# 3_3V2_5A_Microcontroller_Power.net
KiCad netlist of a schematic drawn in Altium Designer
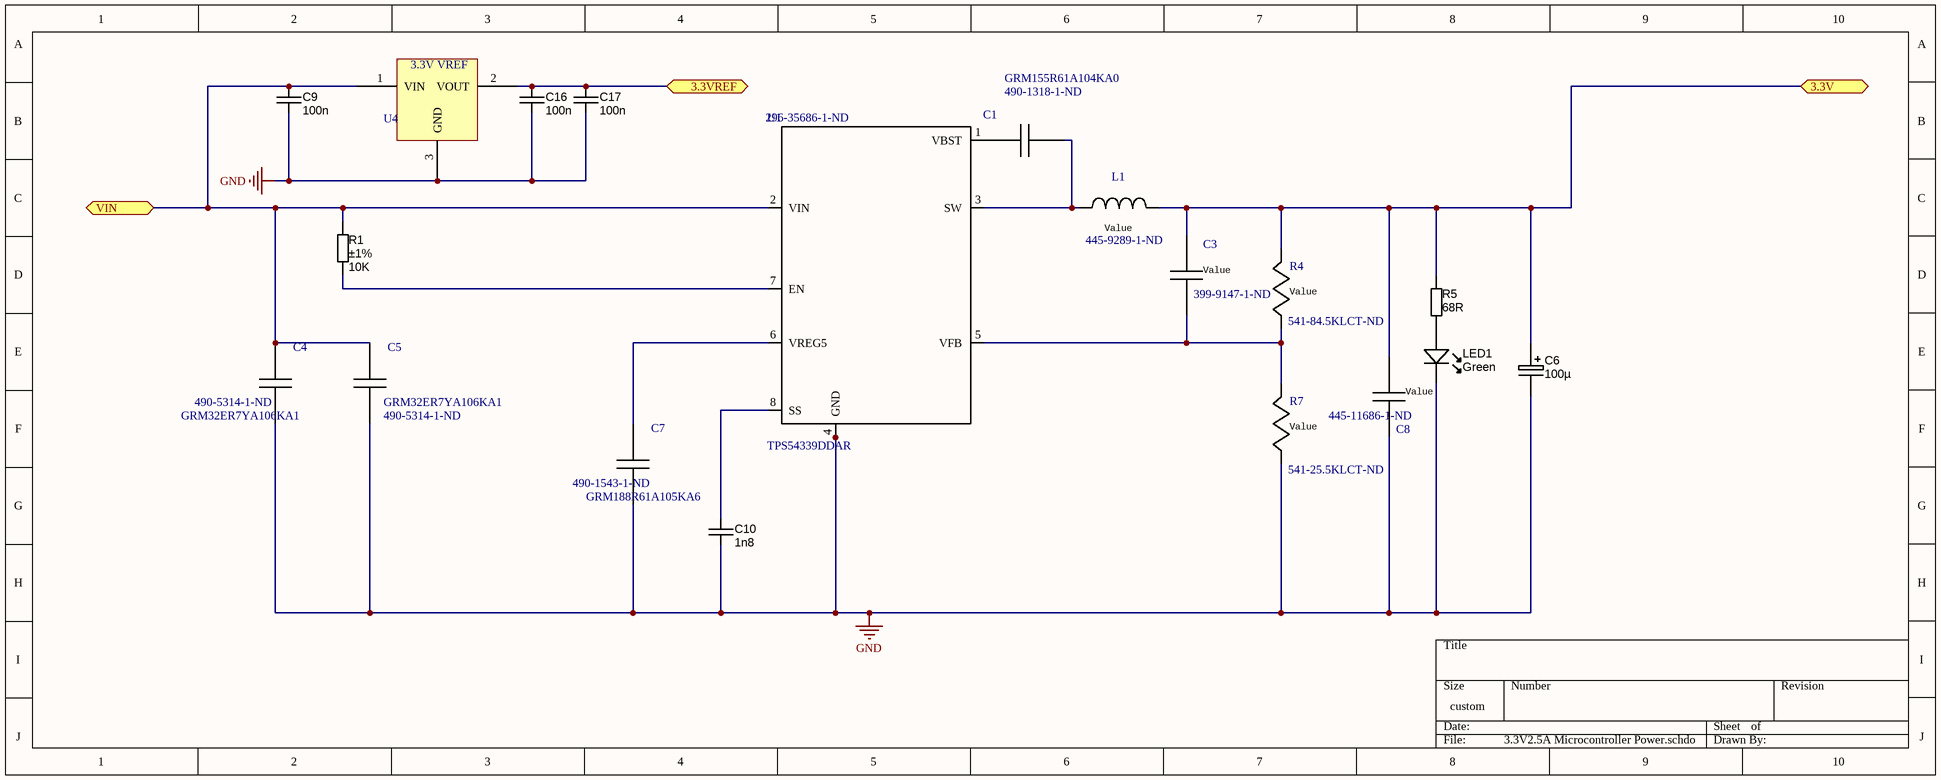
[diagram p0: 3.3V2.5A Microcontroller Power.schdoc]

(export (version "E")
  (design (tool "Eeschema 10.0.6"))
  (components
    (comp (ref "C1")
      (value "GRM155R61A104KA0")
      (footprint "0402")
      (description "Imported")
      (fields
        (field (name "MANUFACTURER_PART_NUMBER") "GRM155R61A104KA01D")
        (field (name "SUPPLIER PART NUMBER 1") "490-1318-1-ND")
      )
      (libsource (lib "LIB1") (part "GRM155R61A104KA0"))
    )
    (comp (ref "C3")
      (value "Value")
      (footprint "0805")
      (description "Imported")
      (fields
        (field (name "MANUFACTURER_PART_NUMBER") "C0805C100M4GACTU")
        (field (name "SUPPLIER PART NUMBER 1") "399-9147-1-ND")
      )
      (libsource (lib "LIB1") (part "C0805C100M4GACTU"))
    )
    (comp (ref "C4")
      (value "GRM32ER7YA106KA1")
      (footprint "1210_280")
      (description "Imported")
      (fields
        (field (name "MANUFACTURER_PART_NUMBER") "GRM32ER7YA106KA12L")
        (field (name "SUPPLIER PART NUMBER 1") "490-5314-1-ND")
      )
      (libsource (lib "LIB1") (part "GRM32ER7YA106KA1"))
    )
    (comp (ref "C5")
      (value "GRM32ER7YA106KA1")
      (footprint "1210_280")
      (description "Imported")
      (fields
        (field (name "MANUFACTURER_PART_NUMBER") "GRM32ER7YA106KA12L")
        (field (name "SUPPLIER PART NUMBER 1") "490-5314-1-ND")
      )
      (libsource (lib "LIB1") (part "GRM32ER7YA106KA1"))
    )
    (comp (ref "C6")
      (value "100µ")
      (footprint "CAPMP7343X310N")
      (description "Capacitor SMD Tantalum 100uF 20% 103V  2917")
      (fields
        (field (name "MANUFACTURER PART NUMBER") "T520D107M010ATE080")
        (field (name "TOLERANCE") "±20%")
      )
      (libsource (lib "PBL - Capacitors") (part "CAPTP_100u_2917_10V"))
    )
    (comp (ref "C7")
      (value "GRM188R61A105KA6")
      (footprint "0603")
      (description "Imported")
      (fields
        (field (name "MANUFACTURER_PART_NUMBER") "GRM188R61A105KA61D")
        (field (name "SUPPLIER PART NUMBER 1") "490-1543-1-ND")
      )
      (libsource (lib "LIB1") (part "GRM188R61A105KA6"))
    )
    (comp (ref "C8")
      (value "Value")
      (footprint "1206")
      (description "Imported")
      (fields
        (field (name "MANUFACTURER_PART_NUMBER") "C3216JB1A476M")
        (field (name "SUPPLIER PART NUMBER 1") "445-11686-1-ND")
      )
      (libsource (lib "LIB1") (part "C3216JB1A476M"))
    )
    (comp (ref "C9")
      (value "100n")
      (footprint "CAPC1608X90N")
      (description "Capacitor SMD Cer 100nF 10% 50V X7R 0603")
      (fields
        (field (name "TOLERANCE") "±10%")
        (field (name "MANUFACTURER") "Murata Electronics North America")
      )
      (libsource (lib "PBL - Capacitors") (part "CAPC_100n_0603_X7R_50V_10%"))
    )
    (comp (ref "C10")
      (value "1n8")
      (footprint "CAPC2012X135N")
      (description "Capacitor SMD Cer 1.8nF 10% 50V X7R 0805")
      (fields (field (name "TOLERANCE") "±10%") (field (name "Comment") "approved sub OK"))
      (libsource (lib "PBL - Capacitors") (part "CAPC_1n8_50V_0805"))
    )
    (comp (ref "C16")
      (value "100n")
      (footprint "CAPC1608X90N")
      (description "Capacitor SMD Cer 100nF 10% 50V X7R 0603")
      (fields
        (field (name "TOLERANCE") "±10%")
        (field (name "MANUFACTURER") "Murata Electronics North America")
      )
      (libsource (lib "PBL - Capacitors") (part "CAPC_100n_0603_X7R_50V_10%"))
    )
    (comp (ref "C17")
      (value "100n")
      (footprint "CAPC1608X90N")
      (description "Capacitor SMD Cer 100nF 10% 50V X7R 0603")
      (fields
        (field (name "TOLERANCE") "±10%")
        (field (name "MANUFACTURER") "Murata Electronics North America")
      )
      (libsource (lib "PBL - Capacitors") (part "CAPC_100n_0603_X7R_50V_10%"))
    )
    (comp (ref "L1")
      (value "Value")
      (footprint "CLF7045")
      (description "Imported")
      (fields
        (field (name "MANUFACTURER_PART_NUMBER") "CLF7045T-3R3N")
        (field (name "MANUFACTURER") "TDK")
        (field (name "SUPPLIER PART NUMBER 1") "445-9289-1-ND")
      )
      (libsource (lib "LIB1") (part "CLF7045T-3R3N"))
    )
    (comp (ref "LED1")
      (value "Green")
      (footprint "LED-0603-GREEN")
      (description "LED 0603 SMD Green 525nm 350mcd 20mA")
      (libsource (lib "PBL - Light Sources") (part "LED_SMD_Green_0603_525nm_350mcd"))
    )
    (comp (ref "R1")
      (value "10K")
      (footprint "RESC1005X40N")
      (description "Resistor SMD chip 10k Ohm 0.063W 1% 0402")
      (fields (field (name "TOLERANCE") "±1%") (field (name "Comment") "Thick Film"))
      (libsource (lib "PBL - Resistors") (part "RES_10K_0402_1%"))
    )
    (comp (ref "R4")
      (value "Value")
      (footprint "0402")
      (description "Imported")
      (fields
        (field (name "MANUFACTURER_PART_NUMBER") "CRCW040284K5FKED")
        (field (name "SUPPLIER PART NUMBER 1") "541-84.5KLCT-ND")
      )
      (libsource (lib "LIB1") (part "CRCW040284K5FKED"))
    )
    (comp (ref "R5")
      (value "68R")
      (footprint "RESC1005X40N")
      (description "Resistor SMD chip 68 Ohm 0.063W 5% 0402")
      (fields (field (name "TOLERANCE") "±5%") (field (name "Comment") "Thick Film"))
      (libsource (lib "PBL - Resistors") (part "RES_68R_0402_5%"))
    )
    (comp (ref "R7")
      (value "Value")
      (footprint "0402")
      (description "Imported")
      (fields
        (field (name "MANUFACTURER_PART_NUMBER") "CRCW040225K5FKED")
        (field (name "SUPPLIER PART NUMBER 1") "541-25.5KLCT-ND")
      )
      (libsource (lib "LIB1") (part "CRCW040225K5FKED"))
    )
    (comp (ref "U1")
      (value "TPS54339DDAR")
      (footprint "DDA0008E")
      (description "Imported")
      (fields
        (field (name "MANUFACTURER_PART_NUMBER") "TPS54229DDAR")
        (field (name "SUPPLIER PART NUMBER 1") "296-35686-1-ND")
      )
      (libsource (lib "LIB1") (part "TPS54339DDAR"))
    )
    (comp (ref "U4")
      (value "NCP51460SN33T1G")
      (footprint "SOT23-3")
      (description "Series Voltage Reference IC ±1% 20mA TO-236-3, SC-59, SOT-23-3")
      (libsource (lib "PBL - Regulators") (part "VREF_3.3_NCP51460SN33T1G"))
    )
  )
  (nets
    (net (code "1") (name "/3.3V") (class "Default")
      (node (ref "C3") (pin "1") (pinfunction "1_1") (pintype "passive"))
      (node (ref "C6") (pin "1") (pintype "passive"))
      (node (ref "C8") (pin "1") (pinfunction "1_1") (pintype "passive"))
      (node (ref "L1") (pin "1") (pinfunction "1_1") (pintype "passive"))
      (node (ref "R4") (pin "1") (pinfunction "1_1") (pintype "passive"))
      (node (ref "R5") (pin "1") (pinfunction "1_1") (pintype "passive"))
    )
    (net (code "2") (name "/3.3VREF") (class "Default")
      (node (ref "C16") (pin "1") (pintype "passive"))
      (node (ref "C17") (pin "1") (pintype "passive"))
      (node (ref "U4") (pin "2") (pinfunction "VOUT_2") (pintype "passive"))
    )
    (net (code "3") (name "/VIN") (class "Default")
      (node (ref "C4") (pin "1") (pinfunction "1_1") (pintype "passive"))
      (node (ref "C5") (pin "1") (pinfunction "1_1") (pintype "passive"))
      (node (ref "C9") (pin "1") (pintype "passive"))
      (node (ref "R1") (pin "1") (pinfunction "1_1") (pintype "passive"))
      (node (ref "U1") (pin "2") (pinfunction "VIN_2") (pintype "passive"))
      (node (ref "U4") (pin "1") (pinfunction "VIN_1") (pintype "passive"))
    )
    (net (code "4") (name "GND") (class "Default")
      (node (ref "C10") (pin "2") (pintype "passive"))
      (node (ref "C16") (pin "2") (pintype "passive"))
      (node (ref "C17") (pin "2") (pintype "passive"))
      (node (ref "C4") (pin "2") (pinfunction "2_2") (pintype "passive"))
      (node (ref "C5") (pin "2") (pinfunction "2_2") (pintype "passive"))
      (node (ref "C6") (pin "2") (pintype "passive"))
      (node (ref "C7") (pin "2") (pinfunction "2_2") (pintype "passive"))
      (node (ref "C8") (pin "2") (pinfunction "2_2") (pintype "passive"))
      (node (ref "C9") (pin "2") (pintype "passive"))
      (node (ref "LED1") (pin "K") (pinfunction "K_K") (pintype "passive"))
      (node (ref "R7") (pin "2") (pinfunction "2_2") (pintype "passive"))
      (node (ref "U1") (pin "4") (pinfunction "GND_4") (pintype "passive"))
      (node (ref "U1") (pin "9") (pinfunction "GND_9") (pintype "passive"))
      (node (ref "U4") (pin "3") (pinfunction "GND_3") (pintype "passive"))
    )
    (net (code "5") (name "Net-(LED1-PadA)") (class "Default")
      (node (ref "LED1") (pin "A") (pinfunction "A_A") (pintype "passive"))
      (node (ref "R5") (pin "2") (pinfunction "2_2") (pintype "passive"))
    )
    (net (code "6") (name "Net-(U1-EN)") (class "Default")
      (node (ref "R1") (pin "2") (pinfunction "2_2") (pintype "passive"))
      (node (ref "U1") (pin "7") (pinfunction "EN_7") (pintype "passive"))
    )
    (net (code "7") (name "Net-(U1-SS)") (class "Default")
      (node (ref "C10") (pin "1") (pintype "passive"))
      (node (ref "U1") (pin "8") (pinfunction "SS_8") (pintype "passive"))
    )
    (net (code "8") (name "Net-(U1-SW)") (class "Default")
      (node (ref "C1") (pin "2") (pinfunction "2_2") (pintype "passive"))
      (node (ref "L1") (pin "2") (pinfunction "2_2") (pintype "passive"))
      (node (ref "U1") (pin "3") (pinfunction "SW_3") (pintype "passive"))
    )
    (net (code "9") (name "Net-(U1-VBST)") (class "Default")
      (node (ref "C1") (pin "1") (pinfunction "1_1") (pintype "passive"))
      (node (ref "U1") (pin "1") (pinfunction "VBST_1") (pintype "passive"))
    )
    (net (code "10") (name "Net-(U1-VFB)") (class "Default")
      (node (ref "C3") (pin "2") (pinfunction "2_2") (pintype "passive"))
      (node (ref "R4") (pin "2") (pinfunction "2_2") (pintype "passive"))
      (node (ref "R7") (pin "1") (pinfunction "1_1") (pintype "passive"))
      (node (ref "U1") (pin "5") (pinfunction "VFB_5") (pintype "passive"))
    )
    (net (code "11") (name "Net-(U1-VREG5)") (class "Default")
      (node (ref "C7") (pin "1") (pinfunction "1_1") (pintype "passive"))
      (node (ref "U1") (pin "6") (pinfunction "VREG5_6") (pintype "passive"))
    )
  )
)
